# KittyEarsV2_Left.net
KiCad netlist of a schematic drawn in EAGLE
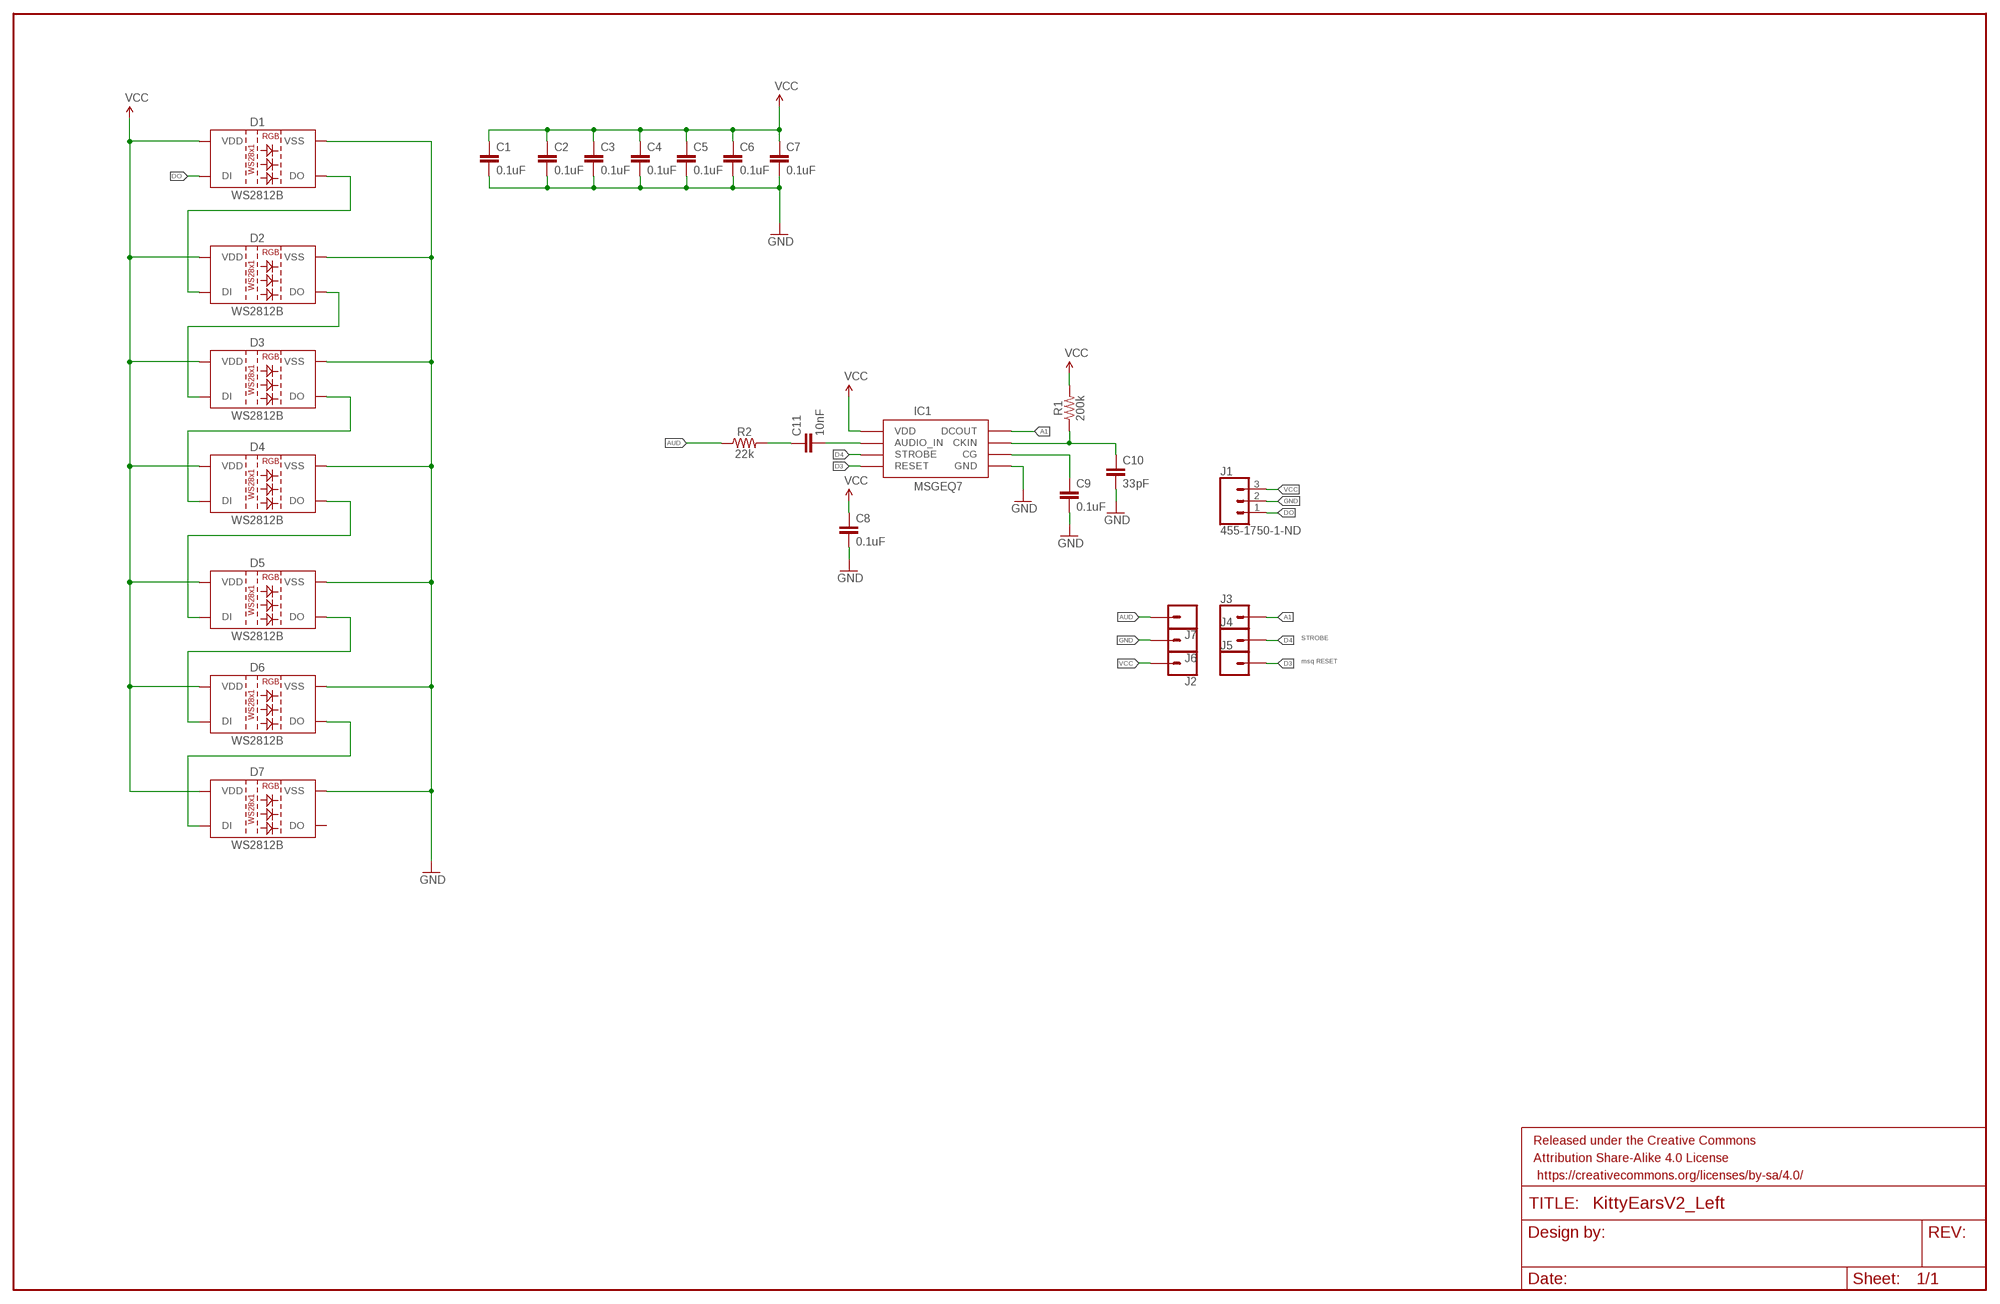
[diagram p0: schematic, sheet 1]

(export (version "E")
  (design (tool "Eeschema 10.0.6"))
  (components
    (comp (ref "C1")
      (value "0.1uF")
      (footprint "eagle-import:0603")
      (libsource (lib "eagle-import") (part "0.1UF-0603-25V-(+80/-20%)"))
    )
    (comp (ref "C2")
      (value "0.1uF")
      (footprint "eagle-import:0603")
      (libsource (lib "eagle-import") (part "0.1UF-0603-25V-(+80/-20%)"))
    )
    (comp (ref "C3")
      (value "0.1uF")
      (footprint "eagle-import:0603")
      (libsource (lib "eagle-import") (part "0.1UF-0603-25V-(+80/-20%)"))
    )
    (comp (ref "C4")
      (value "0.1uF")
      (footprint "eagle-import:0603")
      (libsource (lib "eagle-import") (part "0.1UF-0603-25V-(+80/-20%)"))
    )
    (comp (ref "C5")
      (value "0.1uF")
      (footprint "eagle-import:0603")
      (libsource (lib "eagle-import") (part "0.1UF-0603-25V-(+80/-20%)"))
    )
    (comp (ref "C6")
      (value "0.1uF")
      (footprint "eagle-import:0603")
      (libsource (lib "eagle-import") (part "0.1UF-0603-25V-(+80/-20%)"))
    )
    (comp (ref "C7")
      (value "0.1uF")
      (footprint "eagle-import:0603")
      (libsource (lib "eagle-import") (part "0.1UF-0603-25V-(+80/-20%)"))
    )
    (comp (ref "C8")
      (value "0.1uF")
      (footprint "eagle-import:0603")
      (libsource (lib "eagle-import") (part "0.1UF-0603-25V-(+80/-20%)"))
    )
    (comp (ref "C9")
      (value "0.1uF")
      (footprint "eagle-import:0603")
      (libsource (lib "eagle-import") (part "0.1UF-0603-25V-(+80/-20%)"))
    )
    (comp (ref "C10")
      (value "33pF")
      (footprint "eagle-import:0603")
      (libsource (lib "eagle-import") (part "33PF-0603-50V-5%"))
    )
    (comp (ref "C11")
      (value "10nF")
      (footprint "eagle-import:0603")
      (libsource (lib "eagle-import") (part "10NF-0603-50V-10%"))
    )
    (comp (ref "D1")
      (value "WS2812B")
      (footprint "eagle-import:WS2812B")
      (libsource (lib "eagle-import") (part "WS2812B"))
    )
    (comp (ref "D2")
      (value "WS2812B")
      (footprint "eagle-import:WS2812B")
      (libsource (lib "eagle-import") (part "WS2812B"))
    )
    (comp (ref "D3")
      (value "WS2812B")
      (footprint "eagle-import:WS2812B")
      (libsource (lib "eagle-import") (part "WS2812B"))
    )
    (comp (ref "D4")
      (value "WS2812B")
      (footprint "eagle-import:WS2812B")
      (libsource (lib "eagle-import") (part "WS2812B"))
    )
    (comp (ref "D5")
      (value "WS2812B")
      (footprint "eagle-import:WS2812B")
      (libsource (lib "eagle-import") (part "WS2812B"))
    )
    (comp (ref "D6")
      (value "WS2812B")
      (footprint "eagle-import:WS2812B")
      (libsource (lib "eagle-import") (part "WS2812B"))
    )
    (comp (ref "D7")
      (value "WS2812B")
      (footprint "eagle-import:WS2812B")
      (libsource (lib "eagle-import") (part "WS2812B"))
    )
    (comp (ref "FRAME1")
      (value "FRAME-LEDGER")
      (footprint "eagle-import:CREATIVE_COMMONS")
      (libsource (lib "eagle-import") (part "FRAME-LEDGER"))
    )
    (comp (ref "IC1")
      (value "MSGEQ7N")
      (footprint "eagle-import:SO08")
      (libsource (lib "eagle-import") (part "MSGEQ7SOIC"))
    )
    (comp (ref "J1")
      (value "455-1750-1-ND")
      (footprint "eagle-import:1X03")
      (libsource (lib "eagle-import") (part "CONN_03"))
    )
    (comp (ref "J2")
      (value "CONN_01")
      (footprint "eagle-import:1X01")
      (libsource (lib "eagle-import") (part "CONN_01"))
    )
    (comp (ref "J3")
      (value "CONN_01")
      (footprint "eagle-import:1X01")
      (libsource (lib "eagle-import") (part "CONN_01"))
    )
    (comp (ref "J4")
      (value "CONN_01")
      (footprint "eagle-import:1X01")
      (libsource (lib "eagle-import") (part "CONN_01"))
    )
    (comp (ref "J5")
      (value "CONN_01")
      (footprint "eagle-import:1X01")
      (libsource (lib "eagle-import") (part "CONN_01"))
    )
    (comp (ref "J6")
      (value "CONN_01")
      (footprint "eagle-import:1X01")
      (libsource (lib "eagle-import") (part "CONN_01"))
    )
    (comp (ref "J7")
      (value "CONN_01")
      (footprint "eagle-import:1X01")
      (libsource (lib "eagle-import") (part "CONN_01"))
    )
    (comp (ref "R1")
      (value "200k")
      (footprint "eagle-import:0603")
      (libsource (lib "eagle-import") (part "200KOHM-0603-1/10W-1%"))
    )
    (comp (ref "R2")
      (value "22k")
      (footprint "eagle-import:0603")
      (libsource (lib "eagle-import") (part "22KOHM-0603-1/10W-1%"))
    )
  )
  (nets
    (net (code "1") (name "A1") (class "Default")
      (node (ref "IC1") (pin "3") (pinfunction "DCOUT_3") (pintype "bidirectional"))
      (node (ref "J3") (pin "1") (pinfunction "1_1") (pintype "passive"))
    )
    (net (code "2") (name "AUD") (class "Default")
      (node (ref "J7") (pin "1") (pinfunction "1_1") (pintype "passive"))
      (node (ref "R2") (pin "1") (pinfunction "1_1") (pintype "passive"))
    )
    (net (code "3") (name "D3") (class "Default")
      (node (ref "IC1") (pin "7") (pinfunction "RESET_7") (pintype "input"))
      (node (ref "J5") (pin "1") (pinfunction "1_1") (pintype "passive"))
    )
    (net (code "4") (name "D4") (class "Default")
      (node (ref "IC1") (pin "4") (pinfunction "STROBE_4") (pintype "input"))
      (node (ref "J4") (pin "1") (pinfunction "1_1") (pintype "passive"))
    )
    (net (code "5") (name "DO") (class "Default")
      (node (ref "D1") (pin "4") (pinfunction "DI_4") (pintype "bidirectional"))
      (node (ref "J1") (pin "1") (pinfunction "1_1") (pintype "passive"))
    )
    (net (code "6") (name "GND") (class "Default")
      (node (ref "C1") (pin "2") (pinfunction "2_2") (pintype "passive"))
      (node (ref "C10") (pin "2") (pinfunction "2_2") (pintype "passive"))
      (node (ref "C2") (pin "2") (pinfunction "2_2") (pintype "passive"))
      (node (ref "C3") (pin "2") (pinfunction "2_2") (pintype "passive"))
      (node (ref "C4") (pin "2") (pinfunction "2_2") (pintype "passive"))
      (node (ref "C5") (pin "2") (pinfunction "2_2") (pintype "passive"))
      (node (ref "C6") (pin "2") (pinfunction "2_2") (pintype "passive"))
      (node (ref "C7") (pin "2") (pinfunction "2_2") (pintype "passive"))
      (node (ref "C8") (pin "2") (pinfunction "2_2") (pintype "passive"))
      (node (ref "C9") (pin "2") (pinfunction "2_2") (pintype "passive"))
      (node (ref "D1") (pin "3") (pinfunction "VSS_3") (pintype "bidirectional"))
      (node (ref "D2") (pin "3") (pinfunction "VSS_3") (pintype "bidirectional"))
      (node (ref "D3") (pin "3") (pinfunction "VSS_3") (pintype "bidirectional"))
      (node (ref "D4") (pin "3") (pinfunction "VSS_3") (pintype "bidirectional"))
      (node (ref "D5") (pin "3") (pinfunction "VSS_3") (pintype "bidirectional"))
      (node (ref "D6") (pin "3") (pinfunction "VSS_3") (pintype "bidirectional"))
      (node (ref "D7") (pin "3") (pinfunction "VSS_3") (pintype "bidirectional"))
      (node (ref "IC1") (pin "2") (pinfunction "GND_2") (pintype "bidirectional"))
      (node (ref "J1") (pin "2") (pinfunction "2_2") (pintype "passive"))
      (node (ref "J6") (pin "1") (pinfunction "1_1") (pintype "passive"))
    )
    (net (code "7") (name "Net-(C11-Pad1)") (class "Default")
      (node (ref "C11") (pin "1") (pinfunction "1_1") (pintype "passive"))
      (node (ref "R2") (pin "2") (pinfunction "2_2") (pintype "passive"))
    )
    (net (code "8") (name "Net-(D1-DO)") (class "Default")
      (node (ref "D1") (pin "2") (pinfunction "DO_2") (pintype "bidirectional"))
      (node (ref "D2") (pin "4") (pinfunction "DI_4") (pintype "bidirectional"))
    )
    (net (code "9") (name "Net-(D2-DO)") (class "Default")
      (node (ref "D2") (pin "2") (pinfunction "DO_2") (pintype "bidirectional"))
      (node (ref "D3") (pin "4") (pinfunction "DI_4") (pintype "bidirectional"))
    )
    (net (code "10") (name "Net-(D3-DO)") (class "Default")
      (node (ref "D3") (pin "2") (pinfunction "DO_2") (pintype "bidirectional"))
      (node (ref "D4") (pin "4") (pinfunction "DI_4") (pintype "bidirectional"))
    )
    (net (code "11") (name "Net-(D4-DO)") (class "Default")
      (node (ref "D4") (pin "2") (pinfunction "DO_2") (pintype "bidirectional"))
      (node (ref "D5") (pin "4") (pinfunction "DI_4") (pintype "bidirectional"))
    )
    (net (code "12") (name "Net-(D5-DO)") (class "Default")
      (node (ref "D5") (pin "2") (pinfunction "DO_2") (pintype "bidirectional"))
      (node (ref "D6") (pin "4") (pinfunction "DI_4") (pintype "bidirectional"))
    )
    (net (code "13") (name "Net-(D6-DO)") (class "Default")
      (node (ref "D6") (pin "2") (pinfunction "DO_2") (pintype "bidirectional"))
      (node (ref "D7") (pin "4") (pinfunction "DI_4") (pintype "bidirectional"))
    )
    (net (code "14") (name "Net-(IC1-AUDIO_IN)") (class "Default")
      (node (ref "C11") (pin "2") (pinfunction "2_2") (pintype "passive"))
      (node (ref "IC1") (pin "5") (pinfunction "AUDIO_IN_5") (pintype "input"))
    )
    (net (code "15") (name "Net-(IC1-CG)") (class "Default")
      (node (ref "C9") (pin "1") (pinfunction "1_1") (pintype "passive"))
      (node (ref "IC1") (pin "6") (pinfunction "CG_6") (pintype "bidirectional"))
    )
    (net (code "16") (name "Net-(IC1-CKIN)") (class "Default")
      (node (ref "C10") (pin "1") (pinfunction "1_1") (pintype "passive"))
      (node (ref "IC1") (pin "8") (pinfunction "CKIN_8") (pintype "bidirectional"))
      (node (ref "R1") (pin "1") (pinfunction "1_1") (pintype "passive"))
    )
    (net (code "17") (name "VCC") (class "Default")
      (node (ref "C1") (pin "1") (pinfunction "1_1") (pintype "passive"))
      (node (ref "C2") (pin "1") (pinfunction "1_1") (pintype "passive"))
      (node (ref "C3") (pin "1") (pinfunction "1_1") (pintype "passive"))
      (node (ref "C4") (pin "1") (pinfunction "1_1") (pintype "passive"))
      (node (ref "C5") (pin "1") (pinfunction "1_1") (pintype "passive"))
      (node (ref "C6") (pin "1") (pinfunction "1_1") (pintype "passive"))
      (node (ref "C7") (pin "1") (pinfunction "1_1") (pintype "passive"))
      (node (ref "C8") (pin "1") (pinfunction "1_1") (pintype "passive"))
      (node (ref "D1") (pin "1") (pinfunction "VDD_1") (pintype "bidirectional"))
      (node (ref "D2") (pin "1") (pinfunction "VDD_1") (pintype "bidirectional"))
      (node (ref "D3") (pin "1") (pinfunction "VDD_1") (pintype "bidirectional"))
      (node (ref "D4") (pin "1") (pinfunction "VDD_1") (pintype "bidirectional"))
      (node (ref "D5") (pin "1") (pinfunction "VDD_1") (pintype "bidirectional"))
      (node (ref "D6") (pin "1") (pinfunction "VDD_1") (pintype "bidirectional"))
      (node (ref "D7") (pin "1") (pinfunction "VDD_1") (pintype "bidirectional"))
      (node (ref "IC1") (pin "1") (pinfunction "VDD_1") (pintype "input"))
      (node (ref "J1") (pin "3") (pinfunction "3_3") (pintype "passive"))
      (node (ref "J2") (pin "1") (pinfunction "1_1") (pintype "passive"))
      (node (ref "R1") (pin "2") (pinfunction "2_2") (pintype "passive"))
    )
    (net (code "18") (name "unconnected-(D7-DO-Pad2)") (class "Default")
      (node (ref "D7") (pin "2") (pinfunction "DO_2") (pintype "bidirectional"))
    )
  )
)
